# board.net
KiCad netlist of a schematic drawn in EAGLE
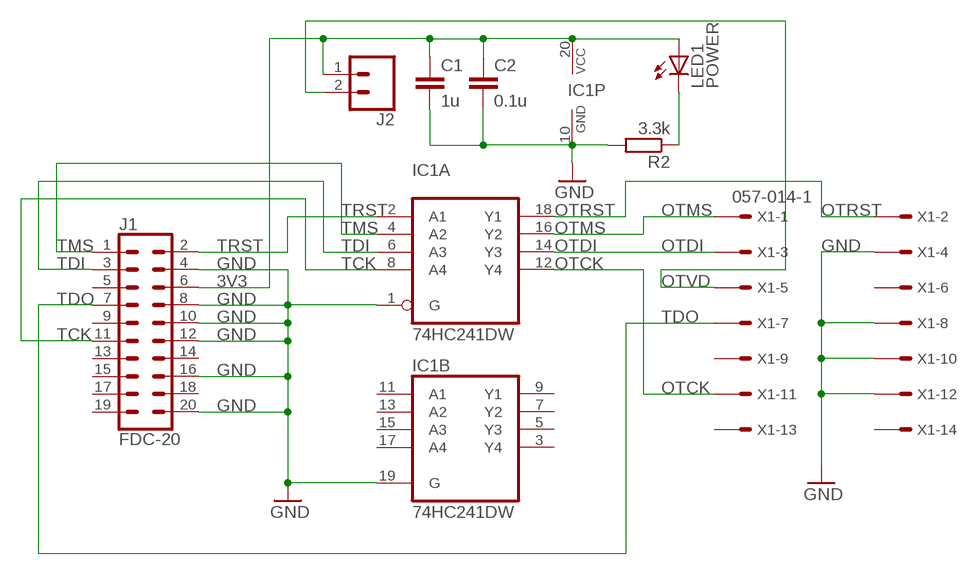
[diagram p0: schematic, sheet 1]

(export (version "E")
  (design (tool "Eeschema 10.0.6"))
  (components
    (comp (ref "C1")
      (value "1u")
      (footprint "eagle-import:C0805")
      (libsource (lib "eagle-import") (part "C-EUC0805"))
    )
    (comp (ref "C2")
      (value "0.1u")
      (footprint "eagle-import:C0805")
      (libsource (lib "eagle-import") (part "C-EUC0805"))
    )
    (comp (ref "IC1")
      (value "74HC241DW")
      (footprint "eagle-import:SO20W")
      (libsource (lib "eagle-import") (part "74241DWHC"))
    )
    (comp (ref "J1")
      (value "FDC-20")
      (footprint "eagle-import:2X10_NOSILK")
      (libsource (lib "eagle-import") (part "CONN_10X2NOSILK"))
    )
    (comp (ref "J2")
      (value "CONN_02")
      (footprint "eagle-import:1X02")
      (libsource (lib "eagle-import") (part "CONN_02"))
    )
    (comp (ref "LED1")
      (value "POWER")
      (footprint "eagle-import:CHIPLED_0805")
      (libsource (lib "eagle-import") (part "LEDCHIPLED_0805"))
    )
    (comp (ref "R2")
      (value "3.3k")
      (footprint "eagle-import:R0805")
      (libsource (lib "eagle-import") (part "R-EU_R0805"))
    )
    (comp (ref "X1")
      (value "057-014-1")
      (footprint "eagle-import:057-014-1")
      (libsource (lib "eagle-import") (part "057-014-1"))
    )
  )
  (nets
    (net (code "1") (name "/3V3") (class "Default")
      (node (ref "C1") (pin "1") (pinfunction "1_1") (pintype "passive"))
      (node (ref "C2") (pin "1") (pinfunction "1_1") (pintype "passive"))
      (node (ref "IC1") (pin "20") (pinfunction "VCC_20") (pintype "power_in"))
      (node (ref "J1") (pin "6") (pinfunction "6_6") (pintype "passive"))
      (node (ref "J2") (pin "1") (pinfunction "1_1") (pintype "passive"))
      (node (ref "LED1") (pin "A") (pinfunction "A_A") (pintype "passive"))
    )
    (net (code "2") (name "/OTCK") (class "Default")
      (node (ref "IC1") (pin "12") (pinfunction "Y4_12") (pintype "tri_state"))
      (node (ref "X1") (pin "11") (pinfunction "S_11") (pintype "passive"))
    )
    (net (code "3") (name "/OTDI") (class "Default")
      (node (ref "IC1") (pin "14") (pinfunction "Y3_14") (pintype "tri_state"))
      (node (ref "X1") (pin "3") (pinfunction "S_3") (pintype "passive"))
    )
    (net (code "4") (name "/OTMS") (class "Default")
      (node (ref "IC1") (pin "16") (pinfunction "Y2_16") (pintype "tri_state"))
      (node (ref "X1") (pin "1") (pinfunction "S_1") (pintype "passive"))
    )
    (net (code "5") (name "/OTRST") (class "Default")
      (node (ref "IC1") (pin "18") (pinfunction "Y1_18") (pintype "tri_state"))
      (node (ref "X1") (pin "2") (pinfunction "S_2") (pintype "passive"))
    )
    (net (code "6") (name "/OTVD") (class "Default")
      (node (ref "J2") (pin "2") (pinfunction "2_2") (pintype "passive"))
      (node (ref "X1") (pin "5") (pinfunction "S_5") (pintype "passive"))
    )
    (net (code "7") (name "/TCK") (class "Default")
      (node (ref "IC1") (pin "8") (pinfunction "A4_8") (pintype "input"))
      (node (ref "J1") (pin "11") (pinfunction "11_11") (pintype "passive"))
    )
    (net (code "8") (name "/TDI") (class "Default")
      (node (ref "IC1") (pin "6") (pinfunction "A3_6") (pintype "input"))
      (node (ref "J1") (pin "3") (pinfunction "3_3") (pintype "passive"))
    )
    (net (code "9") (name "/TDO") (class "Default")
      (node (ref "J1") (pin "7") (pinfunction "7_7") (pintype "passive"))
      (node (ref "X1") (pin "7") (pinfunction "S_7") (pintype "passive"))
    )
    (net (code "10") (name "/TMS") (class "Default")
      (node (ref "IC1") (pin "4") (pinfunction "A2_4") (pintype "input"))
      (node (ref "J1") (pin "1") (pinfunction "1_1") (pintype "passive"))
    )
    (net (code "11") (name "/TRST") (class "Default")
      (node (ref "IC1") (pin "2") (pinfunction "A1_2") (pintype "input"))
      (node (ref "J1") (pin "2") (pinfunction "2_2") (pintype "passive"))
    )
    (net (code "12") (name "GND") (class "Default")
      (node (ref "C1") (pin "2") (pinfunction "2_2") (pintype "passive"))
      (node (ref "C2") (pin "2") (pinfunction "2_2") (pintype "passive"))
      (node (ref "IC1") (pin "1") (pinfunction "G_1") (pintype "input"))
      (node (ref "IC1") (pin "10") (pinfunction "GND_10") (pintype "power_in"))
      (node (ref "IC1") (pin "19") (pinfunction "G_19") (pintype "input"))
      (node (ref "J1") (pin "10") (pinfunction "10_10") (pintype "passive"))
      (node (ref "J1") (pin "12") (pinfunction "12_12") (pintype "passive"))
      (node (ref "J1") (pin "16") (pinfunction "16_16") (pintype "passive"))
      (node (ref "J1") (pin "20") (pinfunction "20_20") (pintype "passive"))
      (node (ref "J1") (pin "4") (pinfunction "4_4") (pintype "passive"))
      (node (ref "J1") (pin "8") (pinfunction "8_8") (pintype "passive"))
      (node (ref "R2") (pin "2") (pinfunction "2_2") (pintype "passive"))
      (node (ref "X1") (pin "10") (pinfunction "S_10") (pintype "passive"))
      (node (ref "X1") (pin "12") (pinfunction "S_12") (pintype "passive"))
      (node (ref "X1") (pin "4") (pinfunction "S_4") (pintype "passive"))
      (node (ref "X1") (pin "8") (pinfunction "S_8") (pintype "passive"))
    )
    (net (code "13") (name "Net-(LED1-PadC)") (class "Default")
      (node (ref "LED1") (pin "C") (pinfunction "C_C") (pintype "passive"))
      (node (ref "R2") (pin "1") (pinfunction "1_1") (pintype "passive"))
    )
    (net (code "14") (name "unconnected-(IC1B-A1-Pad11)") (class "Default")
      (node (ref "IC1") (pin "11") (pinfunction "A1_11") (pintype "input"))
    )
    (net (code "15") (name "unconnected-(IC1B-A2-Pad13)") (class "Default")
      (node (ref "IC1") (pin "13") (pinfunction "A2_13") (pintype "input"))
    )
    (net (code "16") (name "unconnected-(IC1B-A3-Pad15)") (class "Default")
      (node (ref "IC1") (pin "15") (pinfunction "A3_15") (pintype "input"))
    )
    (net (code "17") (name "unconnected-(IC1B-A4-Pad17)") (class "Default")
      (node (ref "IC1") (pin "17") (pinfunction "A4_17") (pintype "input"))
    )
    (net (code "18") (name "unconnected-(IC1B-Y1-Pad9)") (class "Default")
      (node (ref "IC1") (pin "9") (pinfunction "Y1_9") (pintype "tri_state"))
    )
    (net (code "19") (name "unconnected-(IC1B-Y2-Pad7)") (class "Default")
      (node (ref "IC1") (pin "7") (pinfunction "Y2_7") (pintype "tri_state"))
    )
    (net (code "20") (name "unconnected-(IC1B-Y3-Pad5)") (class "Default")
      (node (ref "IC1") (pin "5") (pinfunction "Y3_5") (pintype "tri_state"))
    )
    (net (code "21") (name "unconnected-(IC1B-Y4-Pad3)") (class "Default")
      (node (ref "IC1") (pin "3") (pinfunction "Y4_3") (pintype "tri_state"))
    )
    (net (code "22") (name "unconnected-(J1-Pad5)") (class "Default")
      (node (ref "J1") (pin "5") (pinfunction "5_5") (pintype "passive"))
    )
    (net (code "23") (name "unconnected-(J1-Pad9)") (class "Default")
      (node (ref "J1") (pin "9") (pinfunction "9_9") (pintype "passive"))
    )
    (net (code "24") (name "unconnected-(J1-Pad13)") (class "Default")
      (node (ref "J1") (pin "13") (pinfunction "13_13") (pintype "passive"))
    )
    (net (code "25") (name "unconnected-(J1-Pad14)") (class "Default")
      (node (ref "J1") (pin "14") (pinfunction "14_14") (pintype "passive"))
    )
    (net (code "26") (name "unconnected-(J1-Pad15)") (class "Default")
      (node (ref "J1") (pin "15") (pinfunction "15_15") (pintype "passive"))
    )
    (net (code "27") (name "unconnected-(J1-Pad17)") (class "Default")
      (node (ref "J1") (pin "17") (pinfunction "17_17") (pintype "passive"))
    )
    (net (code "28") (name "unconnected-(J1-Pad18)") (class "Default")
      (node (ref "J1") (pin "18") (pinfunction "18_18") (pintype "passive"))
    )
    (net (code "29") (name "unconnected-(J1-Pad19)") (class "Default")
      (node (ref "J1") (pin "19") (pinfunction "19_19") (pintype "passive"))
    )
    (net (code "30") (name "unconnected-(X1E-S-Pad13)") (class "Default")
      (node (ref "X1") (pin "13") (pinfunction "S_13") (pintype "passive"))
    )
    (net (code "31") (name "unconnected-(X1F-S-Pad14)") (class "Default")
      (node (ref "X1") (pin "14") (pinfunction "S_14") (pintype "passive"))
    )
    (net (code "32") (name "unconnected-(X1K-S-Pad6)") (class "Default")
      (node (ref "X1") (pin "6") (pinfunction "S_6") (pintype "passive"))
    )
    (net (code "33") (name "unconnected-(X1N-S-Pad9)") (class "Default")
      (node (ref "X1") (pin "9") (pinfunction "S_9") (pintype "passive"))
    )
  )
)
